# Flight_controller.net
KiCad netlist of a schematic drawn in EasyEDA
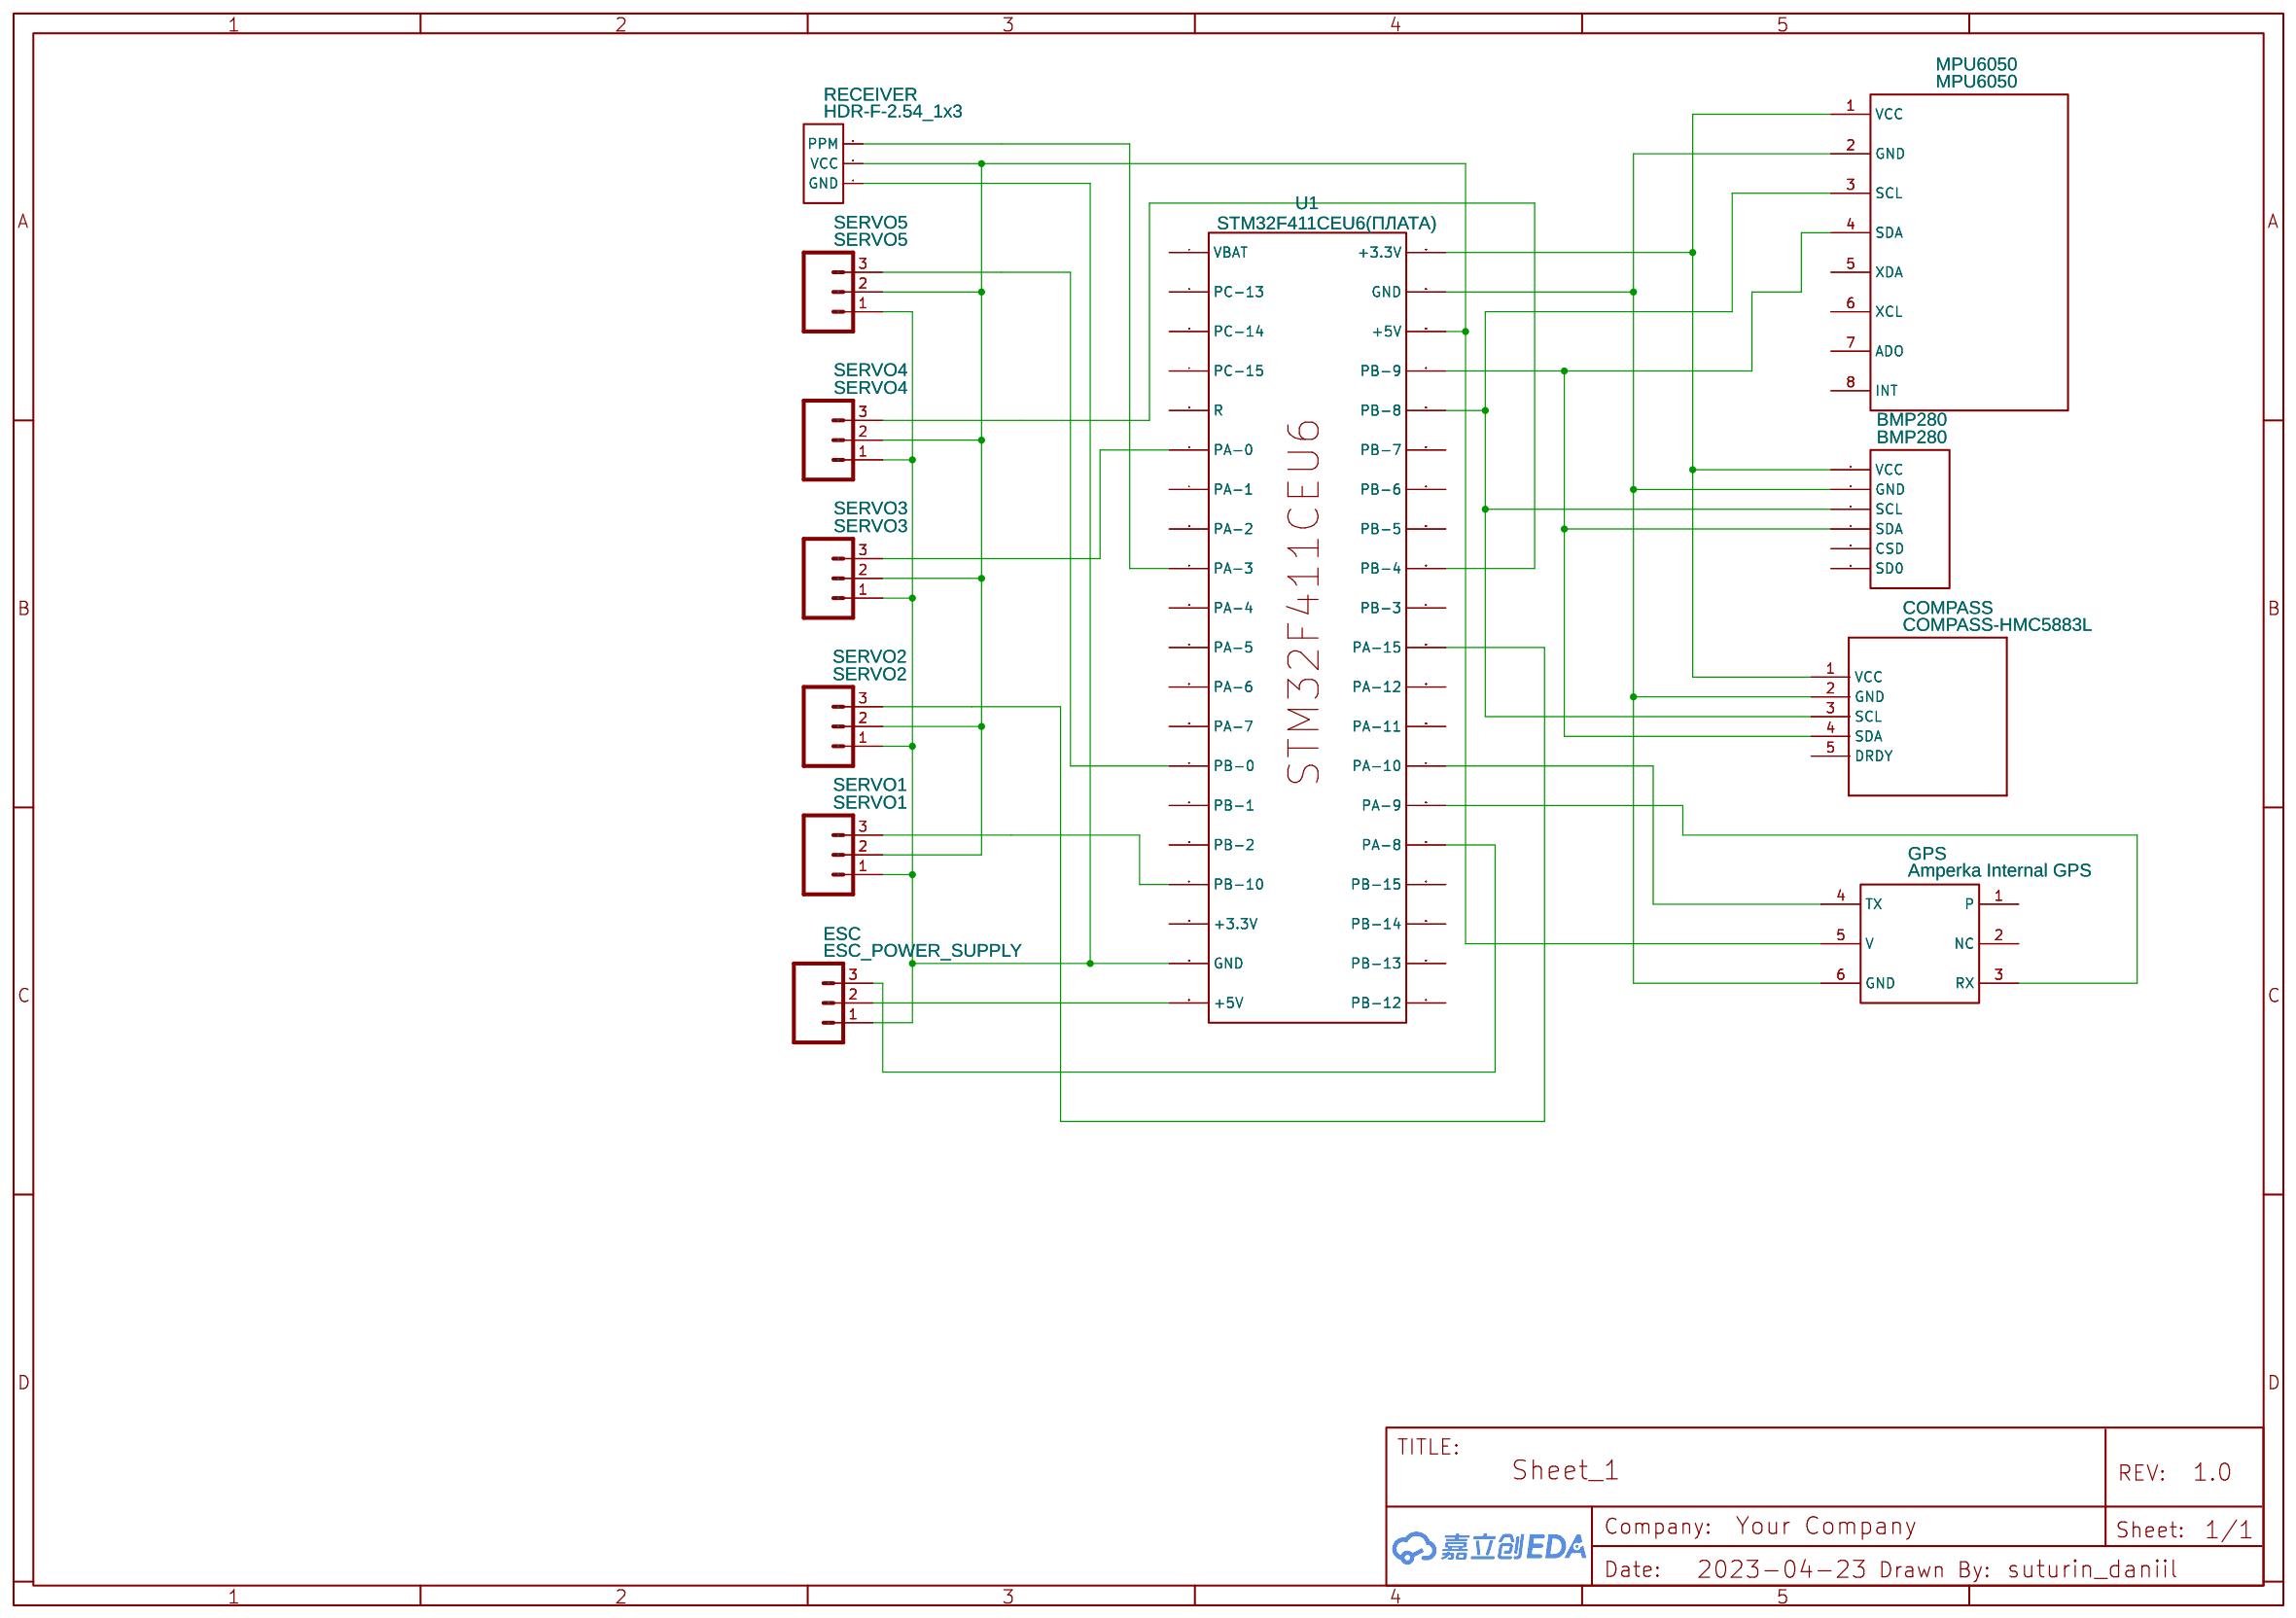
[diagram p0: schematic sheet]

(export (version "E")
  (design (tool "Eeschema 10.0.6"))
  (components
    (comp (ref "BMP280") (value "BMP280") (libsource (lib "") (part "BMP280")))
    (comp (ref "COMPASS") (value "COMPASS-HMC5883L") (libsource (lib "") (part "COMPASS-HMC5883L")))
    (comp (ref "ESC") (value "ESC_POWER_SUPPLY") (libsource (lib "") (part "BALANCE W-03 (2.54MM)_1")))
    (comp (ref "GPS")
      (value "Amperka Internal GPS")
      (fields (field (name "BOM_Manufacturer Part") "Internal GPS"))
      (libsource (lib "") (part "Amperka Internal GPS"))
    )
    (comp (ref "MPU6050") (value "MPU6050") (libsource (lib "") (part "MPU6050")))
    (comp (ref "RECEIVER")
      (value "HDR-F-2.54_1x3")
      (fields (field (name "BOM_Supplier Part") "C146690"))
      (libsource (lib "") (part "HDR-F-2.54_1x3"))
    )
    (comp (ref "SERVO1") (value "SERVO1") (libsource (lib "") (part "BALANCE W-03 (2.54MM)")))
    (comp (ref "SERVO2") (value "SERVO2") (libsource (lib "") (part "BALANCE W-03 (2.54MM)")))
    (comp (ref "SERVO3") (value "SERVO3") (libsource (lib "") (part "BALANCE W-03 (2.54MM)")))
    (comp (ref "SERVO4") (value "SERVO4") (libsource (lib "") (part "BALANCE W-03 (2.54MM)")))
    (comp (ref "SERVO5") (value "SERVO5") (libsource (lib "") (part "BALANCE W-03 (2.54MM)")))
    (comp (ref "U1") (value "STM32F411CEU6(ПЛАТА)") (libsource (lib "") (part "STM32F411CEU6(ПЛАТА)")))
  )
  (nets
    (net (code "1") (name "Net-(BMP280-GND)") (class "Default")
      (node (ref "BMP280") (pin "2") (pinfunction "GND_2") (pintype "unspecified"))
      (node (ref "COMPASS") (pin "2") (pinfunction "GND_2") (pintype "bidirectional"))
      (node (ref "GPS") (pin "6") (pinfunction "GND_6") (pintype "unspecified"))
      (node (ref "MPU6050") (pin "2") (pinfunction "GND_2") (pintype "unspecified"))
      (node (ref "U1") (pin "39") (pinfunction "GND_39") (pintype "unspecified"))
    )
    (net (code "2") (name "Net-(BMP280-SCL)") (class "Default")
      (node (ref "BMP280") (pin "3") (pinfunction "SCL_3") (pintype "unspecified"))
      (node (ref "COMPASS") (pin "3") (pinfunction "SCL_3") (pintype "bidirectional"))
      (node (ref "MPU6050") (pin "3") (pinfunction "SCL_3") (pintype "unspecified"))
      (node (ref "U1") (pin "36") (pinfunction "PB-8_36") (pintype "unspecified"))
    )
    (net (code "3") (name "Net-(BMP280-SDA)") (class "Default")
      (node (ref "BMP280") (pin "4") (pinfunction "SDA_4") (pintype "unspecified"))
      (node (ref "COMPASS") (pin "4") (pinfunction "SDA_4") (pintype "bidirectional"))
      (node (ref "MPU6050") (pin "4") (pinfunction "SDA_4") (pintype "unspecified"))
      (node (ref "U1") (pin "37") (pinfunction "PB-9_37") (pintype "unspecified"))
    )
    (net (code "4") (name "Net-(BMP280-VCC)") (class "Default")
      (node (ref "BMP280") (pin "1") (pinfunction "VCC_1") (pintype "unspecified"))
      (node (ref "COMPASS") (pin "1") (pinfunction "VCC_1") (pintype "bidirectional"))
      (node (ref "MPU6050") (pin "1") (pinfunction "VCC_1") (pintype "unspecified"))
      (node (ref "U1") (pin "40") (pinfunction "+3.3V_40") (pintype "unspecified"))
    )
    (net (code "5") (name "Net-(ESC-Pad2)") (class "Default")
      (node (ref "ESC") (pin "2") (pinfunction "2_2") (pintype "unspecified"))
      (node (ref "U1") (pin "20") (pinfunction "+5V_20") (pintype "unspecified"))
    )
    (net (code "6") (name "Net-(GPS-RX)") (class "Default")
      (node (ref "GPS") (pin "3") (pinfunction "RX_3") (pintype "unspecified"))
      (node (ref "U1") (pin "26") (pinfunction "PA-9_26") (pintype "unspecified"))
    )
    (net (code "7") (name "Net-(GPS-TX)") (class "Default")
      (node (ref "GPS") (pin "4") (pinfunction "TX_4") (pintype "unspecified"))
      (node (ref "U1") (pin "27") (pinfunction "PA-10_27") (pintype "unspecified"))
    )
    (net (code "8") (name "Net-(GPS-V)") (class "Default")
      (node (ref "GPS") (pin "5") (pinfunction "V_5") (pintype "unspecified"))
      (node (ref "RECEIVER") (pin "2") (pinfunction "VCC_2") (pintype "input"))
      (node (ref "SERVO1") (pin "2") (pinfunction "2_2") (pintype "unspecified"))
      (node (ref "SERVO2") (pin "2") (pinfunction "2_2") (pintype "unspecified"))
      (node (ref "SERVO3") (pin "2") (pinfunction "2_2") (pintype "unspecified"))
      (node (ref "SERVO4") (pin "2") (pinfunction "2_2") (pintype "unspecified"))
      (node (ref "SERVO5") (pin "2") (pinfunction "2_2") (pintype "unspecified"))
      (node (ref "U1") (pin "38") (pinfunction "+5V_38") (pintype "unspecified"))
    )
    (net (code "9") (name "Net-(RECEIVER-GND)") (class "Default")
      (node (ref "ESC") (pin "1") (pinfunction "1_1") (pintype "unspecified"))
      (node (ref "RECEIVER") (pin "1") (pinfunction "GND_1") (pintype "input"))
      (node (ref "SERVO1") (pin "1") (pinfunction "1_1") (pintype "unspecified"))
      (node (ref "SERVO2") (pin "1") (pinfunction "1_1") (pintype "unspecified"))
      (node (ref "SERVO3") (pin "1") (pinfunction "1_1") (pintype "unspecified"))
      (node (ref "SERVO4") (pin "1") (pinfunction "1_1") (pintype "unspecified"))
      (node (ref "SERVO5") (pin "1") (pinfunction "1_1") (pintype "unspecified"))
      (node (ref "U1") (pin "19") (pinfunction "GND_19") (pintype "unspecified"))
    )
    (net (code "10") (name "Net-(RECEIVER-PPM)") (class "Default")
      (node (ref "RECEIVER") (pin "3") (pinfunction "PPM_3") (pintype "input"))
      (node (ref "U1") (pin "9") (pinfunction "PA-3_9") (pintype "unspecified"))
    )
    (net (code "11") (name "Net-(U1-PA-0)") (class "Default")
      (node (ref "SERVO3") (pin "3") (pinfunction "3_3") (pintype "unspecified"))
      (node (ref "U1") (pin "6") (pinfunction "PA-0_6") (pintype "unspecified"))
    )
    (net (code "12") (name "Net-(U1-PA-8)") (class "Default")
      (node (ref "ESC") (pin "3") (pinfunction "3_3") (pintype "unspecified"))
      (node (ref "U1") (pin "25") (pinfunction "PA-8_25") (pintype "unspecified"))
    )
    (net (code "13") (name "Net-(U1-PA-15)") (class "Default")
      (node (ref "SERVO2") (pin "3") (pinfunction "3_3") (pintype "unspecified"))
      (node (ref "U1") (pin "30") (pinfunction "PA-15_30") (pintype "unspecified"))
    )
    (net (code "14") (name "Net-(U1-PB-0)") (class "Default")
      (node (ref "SERVO5") (pin "3") (pinfunction "3_3") (pintype "unspecified"))
      (node (ref "U1") (pin "14") (pinfunction "PB-0_14") (pintype "unspecified"))
    )
    (net (code "15") (name "Net-(U1-PB-4)") (class "Default")
      (node (ref "SERVO4") (pin "3") (pinfunction "3_3") (pintype "unspecified"))
      (node (ref "U1") (pin "32") (pinfunction "PB-4_32") (pintype "unspecified"))
    )
    (net (code "16") (name "Net-(U1-PB-10)") (class "Default")
      (node (ref "SERVO1") (pin "3") (pinfunction "3_3") (pintype "unspecified"))
      (node (ref "U1") (pin "17") (pinfunction "PB-10_17") (pintype "unspecified"))
    )
    (net (code "17") (name "unconnected-(BMP280-CSD-Pad5)") (class "Default")
      (node (ref "BMP280") (pin "5") (pinfunction "CSD_5") (pintype "unspecified"))
    )
    (net (code "18") (name "unconnected-(BMP280-SD0-Pad6)") (class "Default")
      (node (ref "BMP280") (pin "6") (pinfunction "SD0_6") (pintype "unspecified"))
    )
    (net (code "19") (name "unconnected-(COMPASS-DRDY-Pad5)") (class "Default")
      (node (ref "COMPASS") (pin "5") (pinfunction "DRDY_5") (pintype "bidirectional"))
    )
    (net (code "20") (name "unconnected-(GPS-NC-Pad2)") (class "Default")
      (node (ref "GPS") (pin "2") (pinfunction "NC_2") (pintype "unspecified"))
    )
    (net (code "21") (name "unconnected-(GPS-P-Pad1)") (class "Default")
      (node (ref "GPS") (pin "1") (pinfunction "P_1") (pintype "unspecified"))
    )
    (net (code "22") (name "unconnected-(MPU6050-ADO-Pad7)") (class "Default")
      (node (ref "MPU6050") (pin "7") (pinfunction "ADO_7") (pintype "unspecified"))
    )
    (net (code "23") (name "unconnected-(MPU6050-INT-Pad8)") (class "Default")
      (node (ref "MPU6050") (pin "8") (pinfunction "INT_8") (pintype "unspecified"))
    )
    (net (code "24") (name "unconnected-(MPU6050-XCL-Pad6)") (class "Default")
      (node (ref "MPU6050") (pin "6") (pinfunction "XCL_6") (pintype "unspecified"))
    )
    (net (code "25") (name "unconnected-(MPU6050-XDA-Pad5)") (class "Default")
      (node (ref "MPU6050") (pin "5") (pinfunction "XDA_5") (pintype "unspecified"))
    )
    (net (code "26") (name "unconnected-(U1-+3.3V-Pad18)") (class "Default")
      (node (ref "U1") (pin "18") (pinfunction "+3.3V_18") (pintype "unspecified"))
    )
    (net (code "27") (name "unconnected-(U1-PA-1-Pad7)") (class "Default")
      (node (ref "U1") (pin "7") (pinfunction "PA-1_7") (pintype "unspecified"))
    )
    (net (code "28") (name "unconnected-(U1-PA-2-Pad8)") (class "Default")
      (node (ref "U1") (pin "8") (pinfunction "PA-2_8") (pintype "unspecified"))
    )
    (net (code "29") (name "unconnected-(U1-PA-4-Pad10)") (class "Default")
      (node (ref "U1") (pin "10") (pinfunction "PA-4_10") (pintype "unspecified"))
    )
    (net (code "30") (name "unconnected-(U1-PA-5-Pad11)") (class "Default")
      (node (ref "U1") (pin "11") (pinfunction "PA-5_11") (pintype "unspecified"))
    )
    (net (code "31") (name "unconnected-(U1-PA-6-Pad12)") (class "Default")
      (node (ref "U1") (pin "12") (pinfunction "PA-6_12") (pintype "unspecified"))
    )
    (net (code "32") (name "unconnected-(U1-PA-7-Pad13)") (class "Default")
      (node (ref "U1") (pin "13") (pinfunction "PA-7_13") (pintype "unspecified"))
    )
    (net (code "33") (name "unconnected-(U1-PA-11-Pad28)") (class "Default")
      (node (ref "U1") (pin "28") (pinfunction "PA-11_28") (pintype "unspecified"))
    )
    (net (code "34") (name "unconnected-(U1-PA-12-Pad29)") (class "Default")
      (node (ref "U1") (pin "29") (pinfunction "PA-12_29") (pintype "unspecified"))
    )
    (net (code "35") (name "unconnected-(U1-PB-1-Pad15)") (class "Default")
      (node (ref "U1") (pin "15") (pinfunction "PB-1_15") (pintype "unspecified"))
    )
    (net (code "36") (name "unconnected-(U1-PB-2-Pad16)") (class "Default")
      (node (ref "U1") (pin "16") (pinfunction "PB-2_16") (pintype "unspecified"))
    )
    (net (code "37") (name "unconnected-(U1-PB-3-Pad31)") (class "Default")
      (node (ref "U1") (pin "31") (pinfunction "PB-3_31") (pintype "unspecified"))
    )
    (net (code "38") (name "unconnected-(U1-PB-5-Pad33)") (class "Default")
      (node (ref "U1") (pin "33") (pinfunction "PB-5_33") (pintype "unspecified"))
    )
    (net (code "39") (name "unconnected-(U1-PB-6-Pad34)") (class "Default")
      (node (ref "U1") (pin "34") (pinfunction "PB-6_34") (pintype "unspecified"))
    )
    (net (code "40") (name "unconnected-(U1-PB-7-Pad35)") (class "Default")
      (node (ref "U1") (pin "35") (pinfunction "PB-7_35") (pintype "unspecified"))
    )
    (net (code "41") (name "unconnected-(U1-PB-12-Pad21)") (class "Default")
      (node (ref "U1") (pin "21") (pinfunction "PB-12_21") (pintype "unspecified"))
    )
    (net (code "42") (name "unconnected-(U1-PB-13-Pad22)") (class "Default")
      (node (ref "U1") (pin "22") (pinfunction "PB-13_22") (pintype "unspecified"))
    )
    (net (code "43") (name "unconnected-(U1-PB-14-Pad23)") (class "Default")
      (node (ref "U1") (pin "23") (pinfunction "PB-14_23") (pintype "unspecified"))
    )
    (net (code "44") (name "unconnected-(U1-PB-15-Pad24)") (class "Default")
      (node (ref "U1") (pin "24") (pinfunction "PB-15_24") (pintype "unspecified"))
    )
    (net (code "45") (name "unconnected-(U1-PC-13-Pad2)") (class "Default")
      (node (ref "U1") (pin "2") (pinfunction "PC-13_2") (pintype "unspecified"))
    )
    (net (code "46") (name "unconnected-(U1-PC-14-Pad3)") (class "Default")
      (node (ref "U1") (pin "3") (pinfunction "PC-14_3") (pintype "unspecified"))
    )
    (net (code "47") (name "unconnected-(U1-PC-15-Pad4)") (class "Default")
      (node (ref "U1") (pin "4") (pinfunction "PC-15_4") (pintype "unspecified"))
    )
    (net (code "48") (name "unconnected-(U1-R-Pad5)") (class "Default")
      (node (ref "U1") (pin "5") (pinfunction "R_5") (pintype "unspecified"))
    )
    (net (code "49") (name "unconnected-(U1-VBAT-Pad1)") (class "Default")
      (node (ref "U1") (pin "1") (pinfunction "VBAT_1") (pintype "unspecified"))
    )
  )
)
